# singlesided.net
KiCad netlist of a schematic drawn in EAGLE
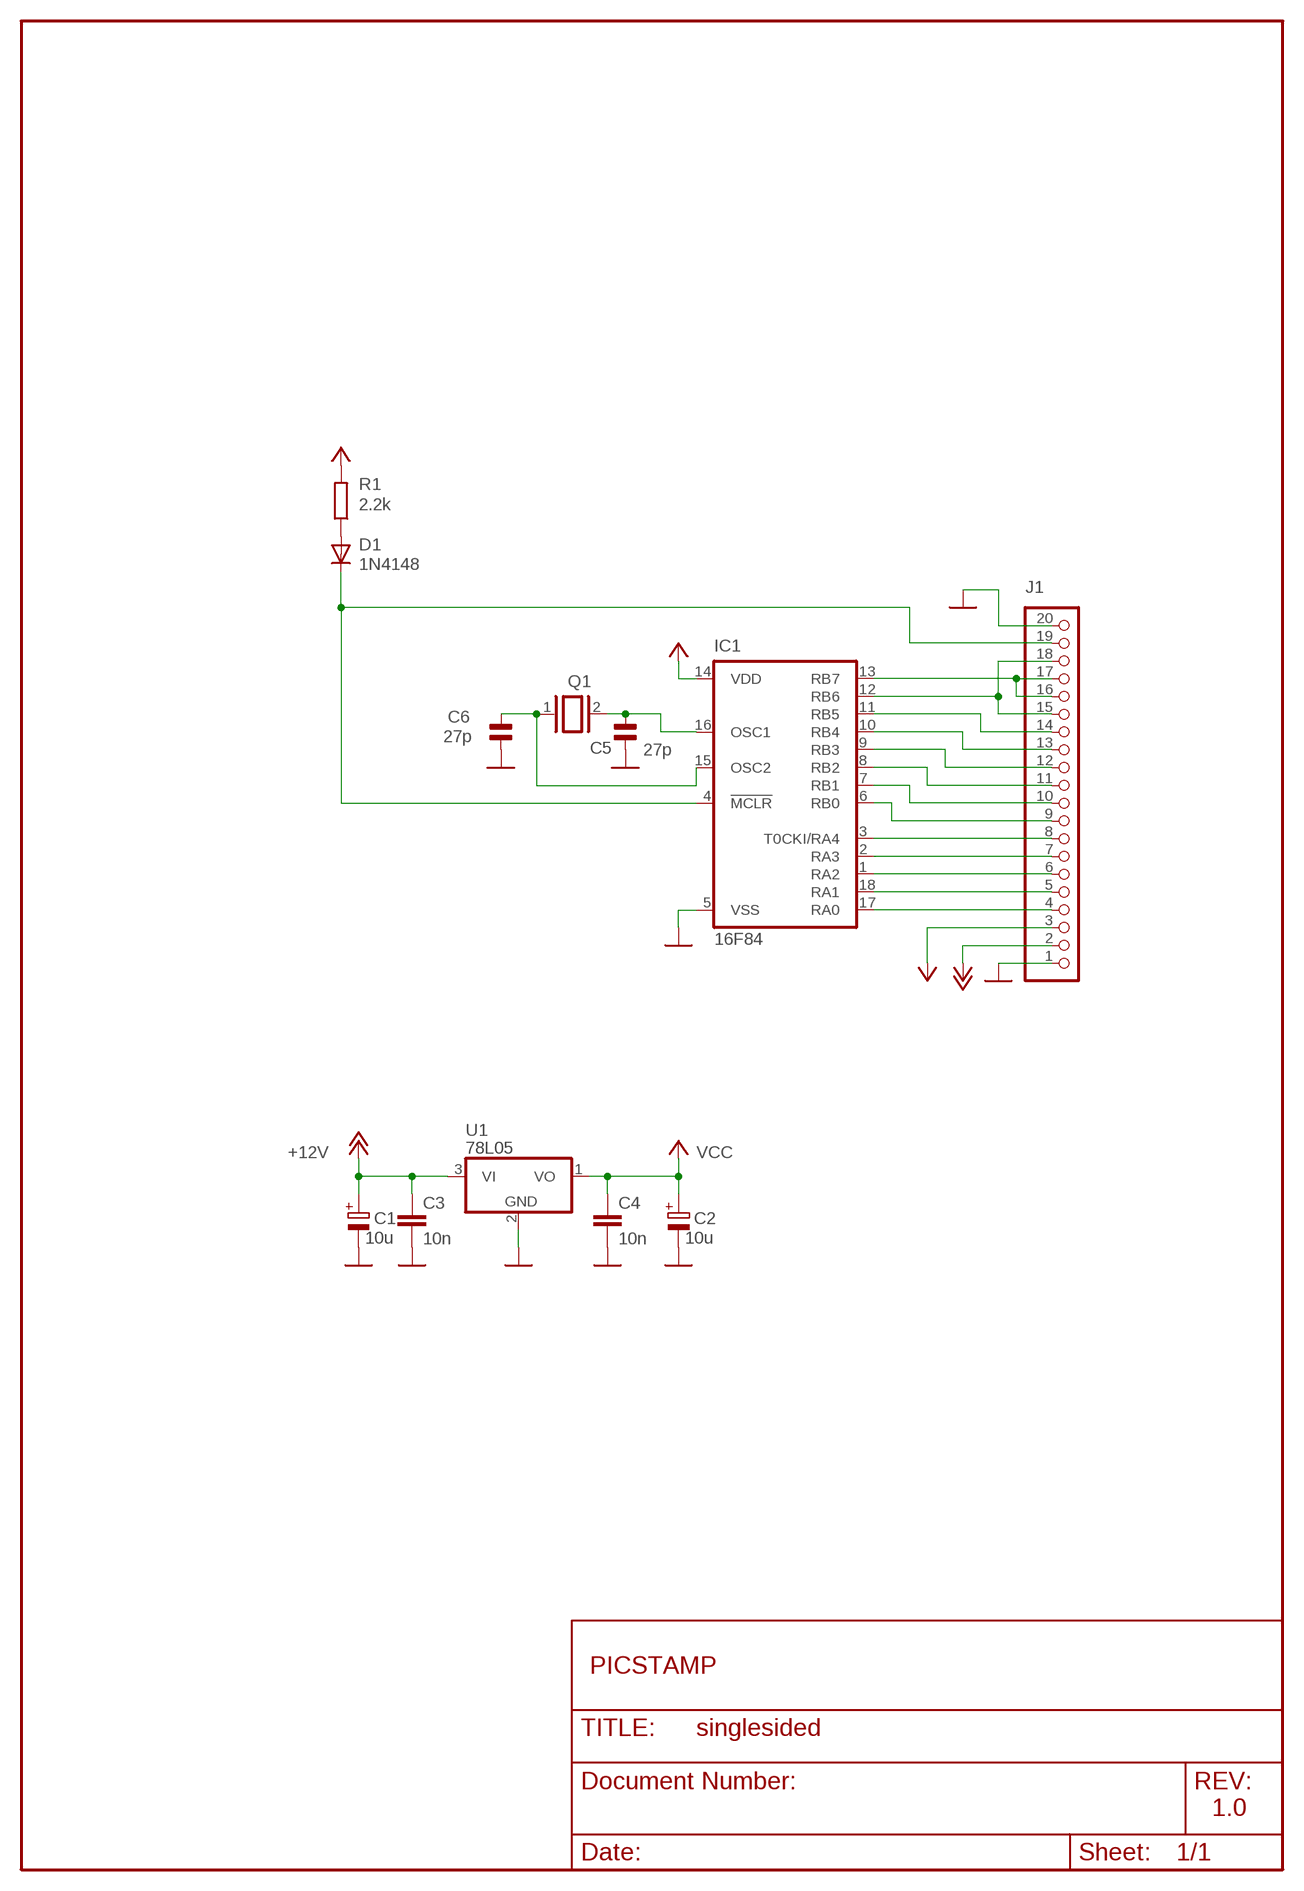
[diagram p0: schematic, sheet 1]

(export (version "E")
  (design (tool "Eeschema 10.0.6"))
  (components
    (comp (ref "C1")
      (value "10u")
      (footprint "eagle-import:E2,5-6")
      (libsource (lib "eagle-import") (part "E2,5-6"))
    )
    (comp (ref "C2")
      (value "10u")
      (footprint "eagle-import:E2,5-6")
      (libsource (lib "eagle-import") (part "E2,5-6"))
    )
    (comp (ref "C3")
      (value "10n")
      (footprint "eagle-import:C025-025X050")
      (libsource (lib "eagle-import") (part "C-EU025-025X050"))
    )
    (comp (ref "C4")
      (value "10n")
      (footprint "eagle-import:C025-025X050")
      (libsource (lib "eagle-import") (part "C-EU025-025X050"))
    )
    (comp (ref "C5")
      (value "27p")
      (footprint "eagle-import:C2,5-2")
      (libsource (lib "eagle-import") (part "C2.5/2"))
    )
    (comp (ref "C6")
      (value "27p")
      (footprint "eagle-import:C2,5-2")
      (libsource (lib "eagle-import") (part "C2.5/2"))
    )
    (comp (ref "D1")
      (value "1N4148")
      (footprint "eagle-import:DO35-10")
      (libsource (lib "eagle-import") (part "1N4148?"))
    )
    (comp (ref "IC1")
      (value "16F84")
      (footprint "eagle-import:DIL18")
      (libsource (lib "eagle-import") (part "PIC16F8P4A"))
    )
    (comp (ref "J1")
      (value "PINHD-1X20")
      (footprint "eagle-import:1X20")
      (libsource (lib "eagle-import") (part "PINHD-1X20"))
    )
    (comp (ref "Q1")
      (value "XTAL/S")
      (footprint "eagle-import:QS")
      (libsource (lib "eagle-import") (part "XTAL/S"))
    )
    (comp (ref "R1")
      (value "2.2k")
      (footprint "eagle-import:0207_10")
      (libsource (lib "eagle-import") (part "R-EU_0207/10"))
    )
    (comp (ref "U1")
      (value "78L05")
      (footprint "eagle-import:TO92")
      (libsource (lib "eagle-import") (part "78LXXZ"))
    )
  )
  (nets
    (net (code "1") (name "+12V") (class "Default")
      (node (ref "C1") (pin "+") (pinfunction "+_+") (pintype "passive"))
      (node (ref "C3") (pin "2") (pinfunction "2_2") (pintype "passive"))
      (node (ref "J1") (pin "2") (pinfunction "2_2") (pintype "passive"))
      (node (ref "U1") (pin "3") (pinfunction "VI_3") (pintype "input"))
    )
    (net (code "2") (name "GND") (class "Default")
      (node (ref "C1") (pin "-") (pinfunction "-_-") (pintype "passive"))
      (node (ref "C2") (pin "-") (pinfunction "-_-") (pintype "passive"))
      (node (ref "C3") (pin "1") (pinfunction "1_1") (pintype "passive"))
      (node (ref "C4") (pin "1") (pinfunction "1_1") (pintype "passive"))
      (node (ref "C5") (pin "1") (pinfunction "1_1") (pintype "passive"))
      (node (ref "C6") (pin "1") (pinfunction "1_1") (pintype "passive"))
      (node (ref "IC1") (pin "5") (pinfunction "VSS_5") (pintype "power_in"))
      (node (ref "J1") (pin "1") (pinfunction "1_1") (pintype "passive"))
      (node (ref "J1") (pin "20") (pinfunction "20_20") (pintype "passive"))
      (node (ref "U1") (pin "2") (pinfunction "GND_2") (pintype "passive"))
    )
    (net (code "3") (name "Net-(D1-C)") (class "Default")
      (node (ref "D1") (pin "K") (pinfunction "C_K") (pintype "passive"))
      (node (ref "IC1") (pin "4") (pinfunction "~{MCLR}_4") (pintype "input"))
      (node (ref "J1") (pin "19") (pinfunction "19_19") (pintype "passive"))
    )
    (net (code "4") (name "Net-(D1-PadA)") (class "Default")
      (node (ref "D1") (pin "A") (pinfunction "A_A") (pintype "passive"))
      (node (ref "R1") (pin "1") (pinfunction "1_1") (pintype "passive"))
    )
    (net (code "5") (name "Net-(IC1-OSC1)") (class "Default")
      (node (ref "C5") (pin "2") (pinfunction "2_2") (pintype "passive"))
      (node (ref "IC1") (pin "16") (pinfunction "OSC1_16") (pintype "input"))
      (node (ref "Q1") (pin "2") (pinfunction "2_2") (pintype "passive"))
    )
    (net (code "6") (name "Net-(IC1-OSC2)") (class "Default")
      (node (ref "C6") (pin "2") (pinfunction "2_2") (pintype "passive"))
      (node (ref "IC1") (pin "15") (pinfunction "OSC2_15") (pintype "output"))
      (node (ref "Q1") (pin "1") (pinfunction "1_1") (pintype "passive"))
    )
    (net (code "7") (name "Net-(IC1-RA0)") (class "Default")
      (node (ref "IC1") (pin "17") (pinfunction "RA0_17") (pintype "bidirectional"))
      (node (ref "J1") (pin "4") (pinfunction "4_4") (pintype "passive"))
    )
    (net (code "8") (name "Net-(IC1-RA1)") (class "Default")
      (node (ref "IC1") (pin "18") (pinfunction "RA1_18") (pintype "bidirectional"))
      (node (ref "J1") (pin "5") (pinfunction "5_5") (pintype "passive"))
    )
    (net (code "9") (name "Net-(IC1-RA2)") (class "Default")
      (node (ref "IC1") (pin "1") (pinfunction "RA2_1") (pintype "bidirectional"))
      (node (ref "J1") (pin "6") (pinfunction "6_6") (pintype "passive"))
    )
    (net (code "10") (name "Net-(IC1-RA3)") (class "Default")
      (node (ref "IC1") (pin "2") (pinfunction "RA3_2") (pintype "bidirectional"))
      (node (ref "J1") (pin "7") (pinfunction "7_7") (pintype "passive"))
    )
    (net (code "11") (name "Net-(IC1-RB0)") (class "Default")
      (node (ref "IC1") (pin "6") (pinfunction "RB0_6") (pintype "bidirectional"))
      (node (ref "J1") (pin "9") (pinfunction "9_9") (pintype "passive"))
    )
    (net (code "12") (name "Net-(IC1-RB1)") (class "Default")
      (node (ref "IC1") (pin "7") (pinfunction "RB1_7") (pintype "bidirectional"))
      (node (ref "J1") (pin "10") (pinfunction "10_10") (pintype "passive"))
    )
    (net (code "13") (name "Net-(IC1-RB2)") (class "Default")
      (node (ref "IC1") (pin "8") (pinfunction "RB2_8") (pintype "bidirectional"))
      (node (ref "J1") (pin "11") (pinfunction "11_11") (pintype "passive"))
    )
    (net (code "14") (name "Net-(IC1-RB3)") (class "Default")
      (node (ref "IC1") (pin "9") (pinfunction "RB3_9") (pintype "bidirectional"))
      (node (ref "J1") (pin "12") (pinfunction "12_12") (pintype "passive"))
    )
    (net (code "15") (name "Net-(IC1-RB4)") (class "Default")
      (node (ref "IC1") (pin "10") (pinfunction "RB4_10") (pintype "bidirectional"))
      (node (ref "J1") (pin "13") (pinfunction "13_13") (pintype "passive"))
    )
    (net (code "16") (name "Net-(IC1-RB5)") (class "Default")
      (node (ref "IC1") (pin "11") (pinfunction "RB5_11") (pintype "bidirectional"))
      (node (ref "J1") (pin "14") (pinfunction "14_14") (pintype "passive"))
    )
    (net (code "17") (name "Net-(IC1-RB6)") (class "Default")
      (node (ref "IC1") (pin "12") (pinfunction "RB6_12") (pintype "bidirectional"))
      (node (ref "J1") (pin "15") (pinfunction "15_15") (pintype "passive"))
      (node (ref "J1") (pin "18") (pinfunction "18_18") (pintype "passive"))
    )
    (net (code "18") (name "Net-(IC1-RB7)") (class "Default")
      (node (ref "IC1") (pin "13") (pinfunction "RB7_13") (pintype "bidirectional"))
      (node (ref "J1") (pin "16") (pinfunction "16_16") (pintype "passive"))
      (node (ref "J1") (pin "17") (pinfunction "17_17") (pintype "passive"))
    )
    (net (code "19") (name "Net-(IC1-T0CKI{slash}RA4)") (class "Default")
      (node (ref "IC1") (pin "3") (pinfunction "T0CKI/RA4_3") (pintype "bidirectional"))
      (node (ref "J1") (pin "8") (pinfunction "8_8") (pintype "passive"))
    )
    (net (code "20") (name "VCC") (class "Default")
      (node (ref "C2") (pin "+") (pinfunction "+_+") (pintype "passive"))
      (node (ref "C4") (pin "2") (pinfunction "2_2") (pintype "passive"))
      (node (ref "IC1") (pin "14") (pinfunction "VDD_14") (pintype "power_in"))
      (node (ref "J1") (pin "3") (pinfunction "3_3") (pintype "passive"))
      (node (ref "R1") (pin "2") (pinfunction "2_2") (pintype "passive"))
      (node (ref "U1") (pin "1") (pinfunction "VO_1") (pintype "output"))
    )
  )
)
